# Connector.net
KiCad netlist of a schematic drawn in Altium Designer
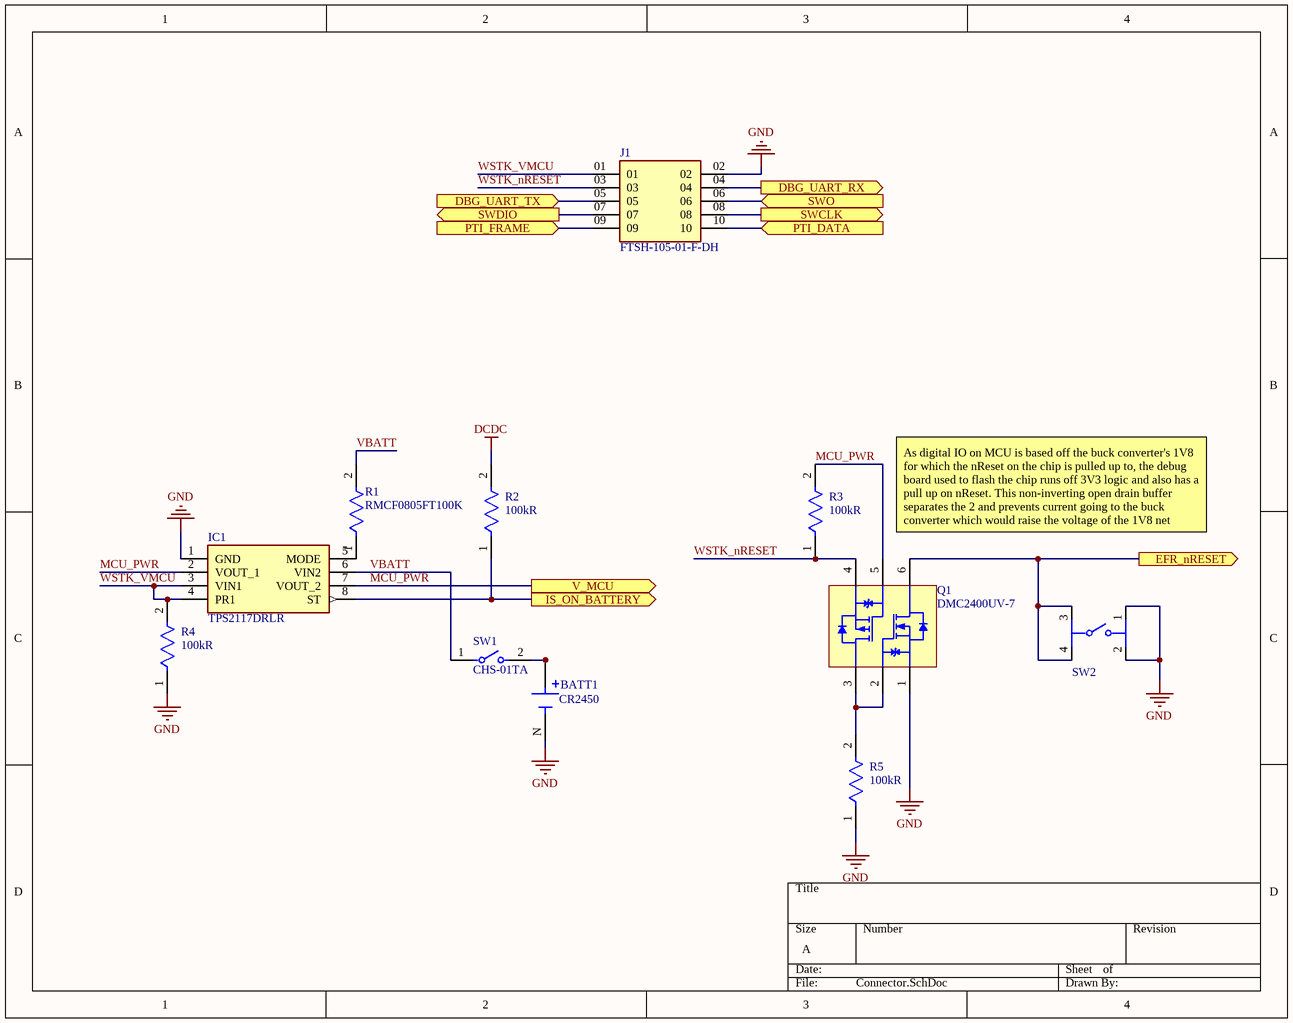
[diagram p0: Connector.SchDoc]

(export (version "E")
  (design (tool "Eeschema 10.0.6"))
  (components
    (comp (ref "BATT1")
      (value "3009")
      (footprint "BAT_3009")
      (description "CR2450 Retainer")
      (fields (field (name "BATTERY") "CR2450"))
      (libsource (lib "University of Waterloo") (part "3009"))
    )
    (comp (ref "IC1")
      (value "TPS2117DRLR")
      (footprint "SamacSys:SOTFL50P160X60-8N")
      (description "Integrated Circuit")
      (fields (field (name "MOUSER PART NUMBER") "595-TPS2117DRLR"))
      (libsource (lib "*") (part "TPS2117DRLR"))
    )
    (comp (ref "J1")
      (value "FTSH-105-01-F-DH")
      (footprint "SimplicityStudio")
      (libsource (lib "SamacSys") (part "SimplicityStudio"))
    )
    (comp (ref "Q1")
      (value "DMC2400UV-7")
      (footprint "DIOD-SOT563-6_V")
      (fields (field (name "MANUFACTURER") "Diodes Inc"))
      (libsource (lib "Altium Content Vault") (part "DIOD-DMC2400UV-SOT563-6"))
    )
    (comp (ref "R1")
      (value "RMCF0805FT100K")
      (footprint "FP-RMCF0805-IPC_C")
      (description "100kΩ ±1% 0.125W 0805 Thick Film Chip Resistor AEC-Q200 compliant")
      (fields (field (name "TOLERANCE") "1%"))
      (libsource (lib "Altium Content Vault") (part "1029c3af85768c4190bb7ad29bc67b5"))
    )
    (comp (ref "R2")
      (value "RMCF0805FT100K")
      (footprint "FP-RMCF0805-IPC_C")
      (description "100kΩ ±1% 0.125W 0805 Thick Film Chip Resistor AEC-Q200 compliant")
      (fields (field (name "RESISTANCE") "100kR") (field (name "TOLERANCE") "1%"))
      (libsource (lib "Altium Content Vault") (part "1029c3af85768c4190bb7ad29bc67b5"))
    )
    (comp (ref "R3")
      (value "RMCF0805FT100K")
      (footprint "FP-RMCF0805-IPC_C")
      (description "100kΩ ±1% 0.125W 0805 Thick Film Chip Resistor AEC-Q200 compliant")
      (fields (field (name "RESISTANCE") "100kR") (field (name "TOLERANCE") "1%"))
      (libsource (lib "Altium Content Vault") (part "1029c3af85768c4190bb7ad29bc67b5"))
    )
    (comp (ref "R4")
      (value "RMCF0805FT100K")
      (footprint "FP-RMCF0805-IPC_C")
      (description "100kΩ ±1% 0.125W 0805 Thick Film Chip Resistor AEC-Q200 compliant")
      (fields (field (name "RESISTANCE") "100kR") (field (name "TOLERANCE") "1%"))
      (libsource (lib "Altium Content Vault") (part "1029c3af85768c4190bb7ad29bc67b5"))
    )
    (comp (ref "R5")
      (value "RMCF0805FT100K")
      (footprint "FP-RMCF0805-IPC_C")
      (description "100kΩ ±1% 0.125W 0805 Thick Film Chip Resistor AEC-Q200 compliant")
      (fields (field (name "RESISTANCE") "100kR") (field (name "TOLERANCE") "1%"))
      (libsource (lib "Altium Content Vault") (part "1029c3af85768c4190bb7ad29bc67b5"))
    )
    (comp (ref "SW1")
      (value "CHS-01TA")
      (footprint "FP-CHS-01TA-MFG")
      (description "SWITCH SLIDE DIP SPST 100MA 6V")
      (fields
        (field (name "OCTOPART") "https://octopart.com/chs-01ta-nidec+copal-52304644")
        (field (name "MANUFACTURER") "Nidec Copal Electronics")
      )
      (libsource (lib "Altium Content Vault") (part "bb27bde45df87f1f469753f287ef5ae"))
    )
    (comp (ref "SW2")
      (value "PTS810SJM250SMTRLFS")
      (footprint "FP-PTS810SJM250SMTRLFS-MFG")
      (description "SWITCH TACTILE SPST-NO 0.05A 16V")
      (libsource (lib "Altium Content Vault") (part "1adf0dd01260c80cf25a44bfd6b99ba"))
    )
  )
  (nets
    (net (code "1") (name "/DBG_UART_RX") (class "Default")
      (node (ref "J1") (pin "04") (pinfunction "04_04") (pintype "passive"))
    )
    (net (code "2") (name "/DBG_UART_TX") (class "Default")
      (node (ref "J1") (pin "05") (pinfunction "05_05") (pintype "passive"))
    )
    (net (code "3") (name "/EFR_nRESET") (class "Default")
      (node (ref "Q1") (pin "6") (pinfunction "D1_6") (pintype "passive"))
      (node (ref "SW2") (pin "3") (pinfunction "3_3") (pintype "passive"))
      (node (ref "SW2") (pin "4") (pinfunction "4_4") (pintype "passive"))
    )
    (net (code "4") (name "/IS_ON_BATTERY") (class "Default")
      (node (ref "IC1") (pin "8") (pinfunction "ST_8") (pintype "output"))
      (node (ref "R2") (pin "1") (pinfunction "1_1") (pintype "passive"))
    )
    (net (code "5") (name "/MCU_PWR") (class "Default")
      (node (ref "IC1") (pin "2") (pinfunction "VOUT_1_2") (pintype "passive"))
      (node (ref "IC1") (pin "7") (pinfunction "VOUT_2_7") (pintype "passive"))
      (node (ref "Q1") (pin "5") (pinfunction "G2_5") (pintype "passive"))
      (node (ref "R3") (pin "2") (pinfunction "2_2") (pintype "passive"))
    )
    (net (code "6") (name "/PTI_DATA") (class "Default")
      (node (ref "J1") (pin "10") (pinfunction "10_10") (pintype "passive"))
    )
    (net (code "7") (name "/PTI_FRAME") (class "Default")
      (node (ref "J1") (pin "09") (pinfunction "09_09") (pintype "passive"))
    )
    (net (code "8") (name "/SWCLK") (class "Default")
      (node (ref "J1") (pin "08") (pinfunction "08_08") (pintype "passive"))
    )
    (net (code "9") (name "/SWDIO") (class "Default")
      (node (ref "J1") (pin "07") (pinfunction "07_07") (pintype "passive"))
    )
    (net (code "10") (name "/SWO") (class "Default")
      (node (ref "J1") (pin "06") (pinfunction "06_06") (pintype "passive"))
    )
    (net (code "11") (name "/VBATT") (class "Default")
      (node (ref "IC1") (pin "6") (pinfunction "VIN2_6") (pintype "passive"))
      (node (ref "R1") (pin "2") (pinfunction "2_2") (pintype "passive"))
      (node (ref "SW1") (pin "1") (pinfunction "1_1") (pintype "passive"))
    )
    (net (code "12") (name "/WSTK_VMCU") (class "Default")
      (node (ref "IC1") (pin "3") (pinfunction "VIN1_3") (pintype "passive"))
      (node (ref "IC1") (pin "4") (pinfunction "PR1_4") (pintype "passive"))
      (node (ref "J1") (pin "01") (pinfunction "01_01") (pintype "passive"))
      (node (ref "R4") (pin "2") (pinfunction "2_2") (pintype "passive"))
    )
    (net (code "13") (name "/WSTK_nRESET") (class "Default")
      (node (ref "J1") (pin "03") (pinfunction "03_03") (pintype "passive"))
      (node (ref "Q1") (pin "4") (pinfunction "S2_4") (pintype "passive"))
      (node (ref "R3") (pin "1") (pinfunction "1_1") (pintype "passive"))
    )
    (net (code "14") (name "DCDC") (class "Default")
      (node (ref "R2") (pin "2") (pinfunction "2_2") (pintype "passive"))
    )
    (net (code "15") (name "GND") (class "Default")
      (node (ref "BATT1") (pin "N") (pinfunction "NEG_N") (pintype "passive"))
      (node (ref "IC1") (pin "1") (pinfunction "GND_1") (pintype "passive"))
      (node (ref "J1") (pin "02") (pinfunction "02_02") (pintype "passive"))
      (node (ref "Q1") (pin "1") (pinfunction "S1_1") (pintype "passive"))
      (node (ref "R4") (pin "1") (pinfunction "1_1") (pintype "passive"))
      (node (ref "R5") (pin "1") (pinfunction "1_1") (pintype "passive"))
      (node (ref "SW2") (pin "1") (pinfunction "1_1") (pintype "passive"))
      (node (ref "SW2") (pin "2") (pinfunction "2_2") (pintype "passive"))
    )
    (net (code "16") (name "Net-(BATT1-POS-PadP1)") (class "Default")
      (node (ref "BATT1") (pin "P1") (pinfunction "POS_P1") (pintype "passive"))
      (node (ref "BATT1") (pin "P2") (pinfunction "POS_P2") (pintype "passive"))
      (node (ref "SW1") (pin "2") (pinfunction "2_2") (pintype "passive"))
    )
    (net (code "17") (name "Net-(IC1-MODE)") (class "Default")
      (node (ref "IC1") (pin "5") (pinfunction "MODE_5") (pintype "passive"))
      (node (ref "R1") (pin "1") (pinfunction "1_1") (pintype "passive"))
    )
    (net (code "18") (name "Net-(Q1-D2)") (class "Default")
      (node (ref "Q1") (pin "2") (pinfunction "G1_2") (pintype "passive"))
      (node (ref "Q1") (pin "3") (pinfunction "D2_3") (pintype "passive"))
      (node (ref "R5") (pin "2") (pinfunction "2_2") (pintype "passive"))
    )
  )
)
